# unoshield-v1.net
KiCad netlist of a schematic drawn in EAGLE
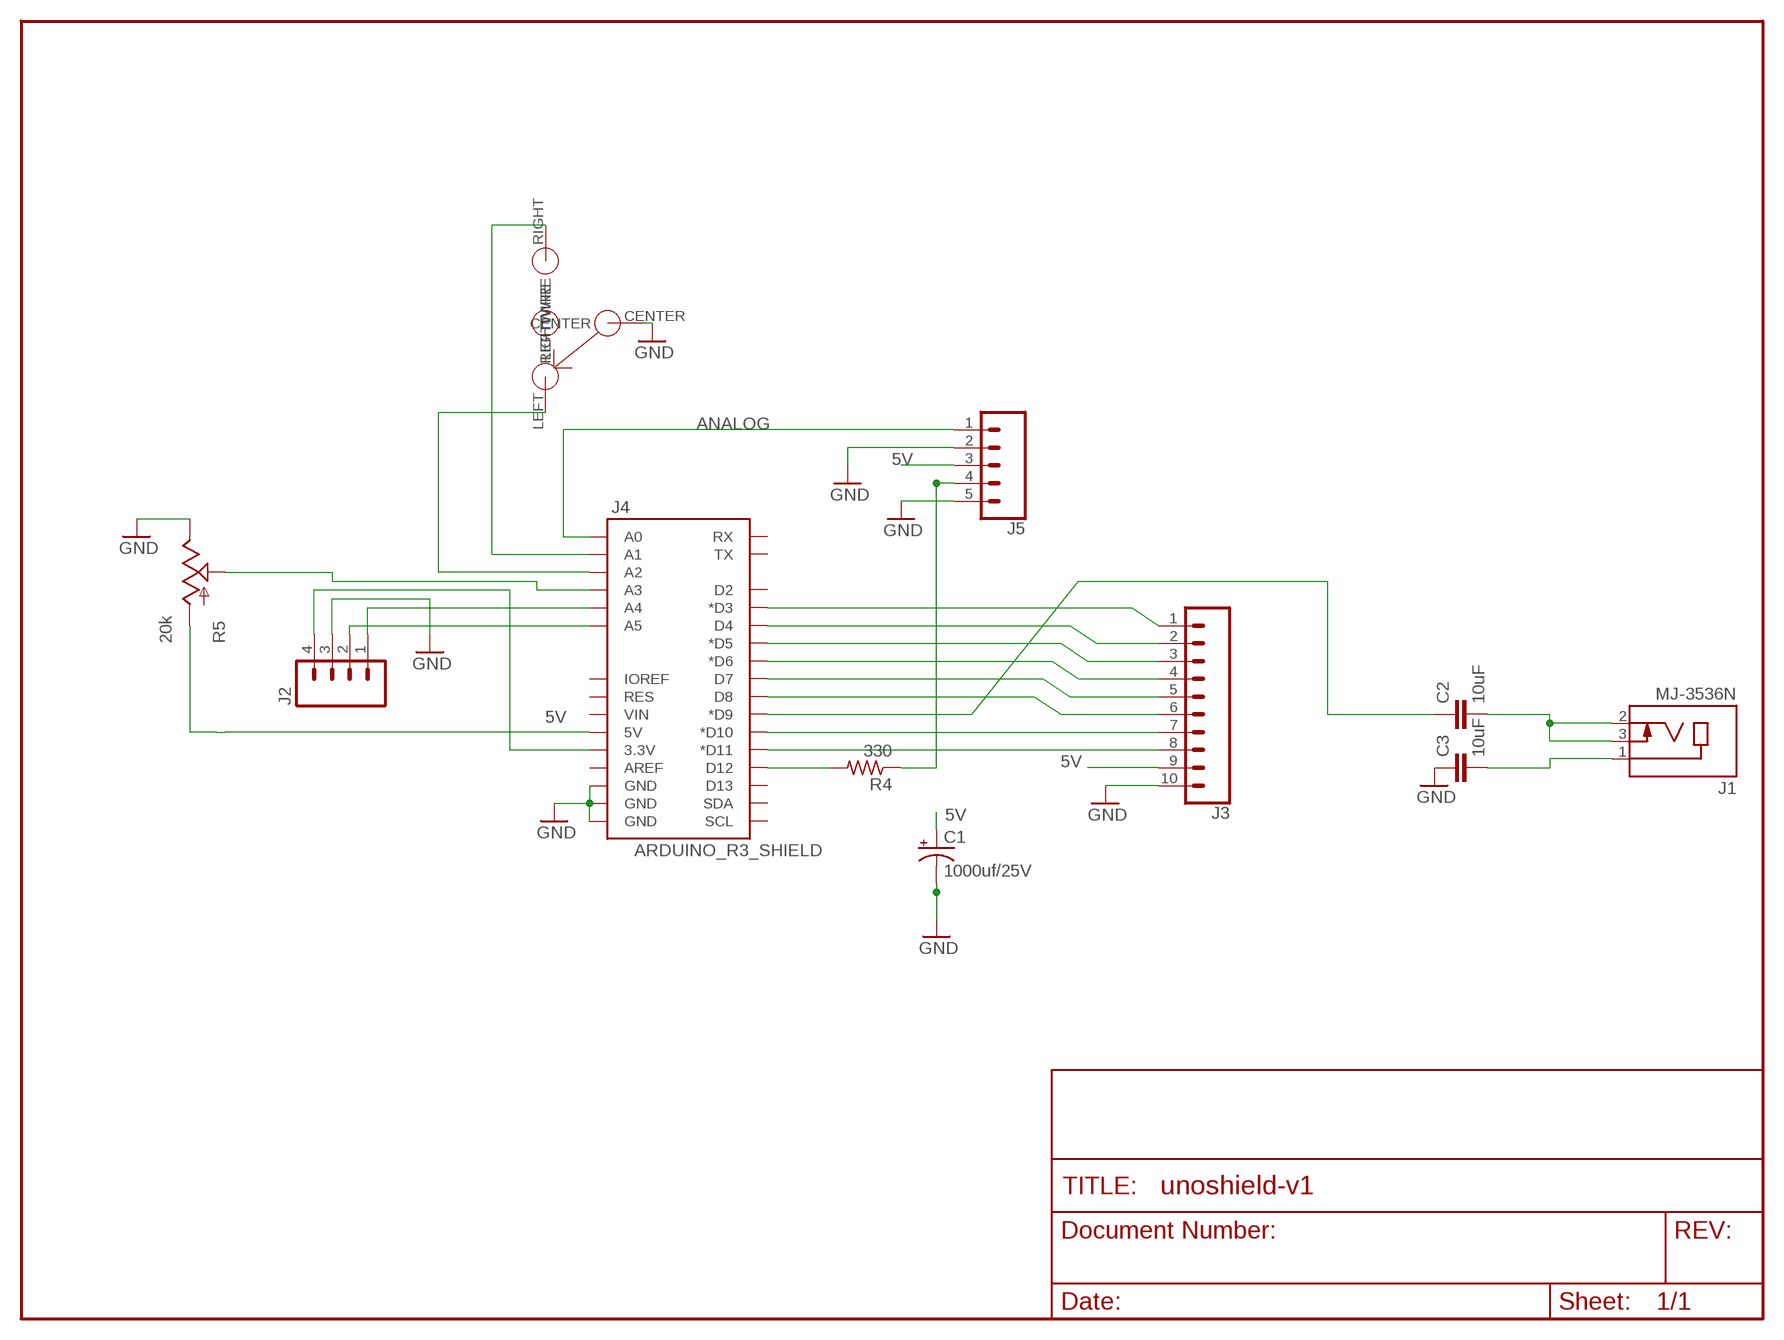
[diagram p0: schematic, sheet 1]

(export (version "E")
  (design (tool "Eeschema 10.0.6"))
  (components
    (comp (ref "C1")
      (value "1000uf/25V")
      (footprint "eagle-import:CPOL-RADIAL-1000UF-25V-KIT")
      (libsource (lib "eagle-import") (part "1000UF-25V(PTH)KIT"))
    )
    (comp (ref "C2")
      (value "10uF")
      (footprint "eagle-import:0805")
      (libsource (lib "eagle-import") (part "10UF-0805-10V-10%"))
    )
    (comp (ref "C3")
      (value "10uF")
      (footprint "eagle-import:0805")
      (libsource (lib "eagle-import") (part "10UF-0805-10V-10%"))
    )
    (comp (ref "J1")
      (value "MJ-3536N")
      (footprint "eagle-import:CUI_MJ-3536N")
      (fields (field (name "MANUFACTURER") "CUI INC"))
      (libsource (lib "eagle-import") (part "MJ-3536N"))
    )
    (comp (ref "J2")
      (value "M04PTH")
      (footprint "eagle-import:1X04")
      (libsource (lib "eagle-import") (part "M04PTH"))
    )
    (comp (ref "J3")
      (value "CONN_10\"")
      (footprint "eagle-import:1X10")
      (libsource (lib "eagle-import") (part "CONN_10{dblquote}"))
    )
    (comp (ref "J4")
      (value "ARDUINO_R3_SHIELD")
      (footprint "eagle-import:UNO_R3_SHIELD")
      (libsource (lib "eagle-import") (part "ARDUINO_R3_SHIELD"))
    )
    (comp (ref "J5")
      (value "CONN_05")
      (footprint "eagle-import:1X05")
      (libsource (lib "eagle-import") (part "CONN_05"))
    )
    (comp (ref "R4")
      (value "330")
      (footprint "eagle-import:R0603")
      (libsource (lib "eagle-import") (part "R-US_R0603"))
    )
    (comp (ref "R5")
      (value "20k")
      (footprint "eagle-import:ALPS_POT_KIT")
      (libsource (lib "eagle-import") (part "POTALPS-KIT"))
    )
    (comp (ref "SW3")
      (value "ON-OFF-ON-360-1013-ND")
      (footprint "eagle-import:360-1013-ND")
      (libsource (lib "eagle-import") (part "ON-OFF-ON-360-1013-ND"))
    )
  )
  (nets
    (net (code "1") (name "/5V") (class "Default")
      (node (ref "C1") (pin "+") (pinfunction "+_+") (pintype "passive"))
      (node (ref "J3") (pin "9") (pinfunction "9_9") (pintype "passive"))
      (node (ref "J4") (pin "5V") (pinfunction "5V_5V") (pintype "bidirectional"))
      (node (ref "J5") (pin "3") (pinfunction "3_3") (pintype "passive"))
      (node (ref "R5") (pin "P$3") (pinfunction "A_P$3") (pintype "passive"))
    )
    (net (code "2") (name "/ANALOG") (class "Default")
      (node (ref "J4") (pin "A0") (pinfunction "A0_A0") (pintype "bidirectional"))
      (node (ref "J5") (pin "1") (pinfunction "1_1") (pintype "passive"))
    )
    (net (code "3") (name "GND") (class "Default")
      (node (ref "C1") (pin "-") (pinfunction "-_-") (pintype "passive"))
      (node (ref "C3") (pin "1") (pinfunction "1_1") (pintype "passive"))
      (node (ref "J2") (pin "3") (pinfunction "3_3") (pintype "passive"))
      (node (ref "J3") (pin "10") (pinfunction "10_10") (pintype "passive"))
      (node (ref "J4") (pin "GND@0") (pinfunction "GND_GND@0") (pintype "bidirectional"))
      (node (ref "J4") (pin "GND@1") (pinfunction "GND_GND@1") (pintype "bidirectional"))
      (node (ref "J4") (pin "GND@2") (pinfunction "GND_GND@2") (pintype "bidirectional"))
      (node (ref "J5") (pin "2") (pinfunction "2_2") (pintype "passive"))
      (node (ref "J5") (pin "5") (pinfunction "5_5") (pintype "passive"))
      (node (ref "R5") (pin "P$1") (pinfunction "E_P$1") (pintype "passive"))
      (node (ref "SW3") (pin "CENTER") (pinfunction "CENTER_CENTER") (pintype "bidirectional"))
    )
    (net (code "4") (name "Net-(C2-Pad2)") (class "Default")
      (node (ref "C2") (pin "2") (pinfunction "2_2") (pintype "passive"))
      (node (ref "J1") (pin "2") (pinfunction "2_2") (pintype "passive"))
      (node (ref "J1") (pin "3") (pinfunction "3_3") (pintype "passive"))
    )
    (net (code "5") (name "Net-(C3-Pad2)") (class "Default")
      (node (ref "C3") (pin "2") (pinfunction "2_2") (pintype "passive"))
      (node (ref "J1") (pin "1") (pinfunction "1_1") (pintype "passive"))
    )
    (net (code "6") (name "Net-(J2-Pad1)") (class "Default")
      (node (ref "J2") (pin "1") (pinfunction "1_1") (pintype "passive"))
      (node (ref "J4") (pin "A4") (pinfunction "A4_A4") (pintype "bidirectional"))
    )
    (net (code "7") (name "Net-(J2-Pad2)") (class "Default")
      (node (ref "J2") (pin "2") (pinfunction "2_2") (pintype "passive"))
      (node (ref "J4") (pin "A5") (pinfunction "A5_A5") (pintype "bidirectional"))
    )
    (net (code "8") (name "Net-(J2-Pad4)") (class "Default")
      (node (ref "J2") (pin "4") (pinfunction "4_4") (pintype "passive"))
      (node (ref "J4") (pin "3.3V") (pinfunction "3.3V_3.3V") (pintype "bidirectional"))
    )
    (net (code "9") (name "Net-(J3-Pad2)") (class "Default")
      (node (ref "J3") (pin "2") (pinfunction "2_2") (pintype "passive"))
      (node (ref "J4") (pin "D4") (pinfunction "D4_D4") (pintype "bidirectional"))
    )
    (net (code "10") (name "Net-(J3-Pad5)") (class "Default")
      (node (ref "J3") (pin "5") (pinfunction "5_5") (pintype "passive"))
      (node (ref "J4") (pin "D7") (pinfunction "D7_D7") (pintype "bidirectional"))
    )
    (net (code "11") (name "Net-(J3-Pad6)") (class "Default")
      (node (ref "J3") (pin "6") (pinfunction "6_6") (pintype "passive"))
      (node (ref "J4") (pin "D8") (pinfunction "D8_D8") (pintype "bidirectional"))
    )
    (net (code "12") (name "Net-(J4-*D3)") (class "Default")
      (node (ref "J3") (pin "1") (pinfunction "1_1") (pintype "passive"))
      (node (ref "J4") (pin "D3") (pinfunction "*D3_D3") (pintype "bidirectional"))
    )
    (net (code "13") (name "Net-(J4-*D5)") (class "Default")
      (node (ref "J3") (pin "3") (pinfunction "3_3") (pintype "passive"))
      (node (ref "J4") (pin "D5") (pinfunction "*D5_D5") (pintype "bidirectional"))
    )
    (net (code "14") (name "Net-(J4-*D6)") (class "Default")
      (node (ref "J3") (pin "4") (pinfunction "4_4") (pintype "passive"))
      (node (ref "J4") (pin "D6") (pinfunction "*D6_D6") (pintype "bidirectional"))
    )
    (net (code "15") (name "Net-(J4-*D9)") (class "Default")
      (node (ref "C2") (pin "1") (pinfunction "1_1") (pintype "passive"))
      (node (ref "J4") (pin "D9") (pinfunction "*D9_D9") (pintype "bidirectional"))
    )
    (net (code "16") (name "Net-(J4-*D10)") (class "Default")
      (node (ref "J3") (pin "7") (pinfunction "7_7") (pintype "passive"))
      (node (ref "J4") (pin "D10") (pinfunction "*D10_D10") (pintype "bidirectional"))
    )
    (net (code "17") (name "Net-(J4-*D11)") (class "Default")
      (node (ref "J3") (pin "8") (pinfunction "8_8") (pintype "passive"))
      (node (ref "J4") (pin "D11") (pinfunction "*D11_D11") (pintype "bidirectional"))
    )
    (net (code "18") (name "Net-(J4-PadD12)") (class "Default")
      (node (ref "J4") (pin "D12") (pinfunction "D12_D12") (pintype "bidirectional"))
      (node (ref "R4") (pin "2") (pinfunction "2_2") (pintype "passive"))
    )
    (net (code "19") (name "Net-(J5-Pad4)") (class "Default")
      (node (ref "J5") (pin "4") (pinfunction "4_4") (pintype "passive"))
      (node (ref "R4") (pin "1") (pinfunction "1_1") (pintype "passive"))
    )
    (net (code "20") (name "Net-(R5-S)") (class "Default")
      (node (ref "J4") (pin "A3") (pinfunction "A3_A3") (pintype "bidirectional"))
      (node (ref "R5") (pin "P$2") (pinfunction "S_P$2") (pintype "passive"))
    )
    (net (code "21") (name "Net-(SW3-LEFTWIRE)") (class "Default")
      (node (ref "J4") (pin "A2") (pinfunction "A2_A2") (pintype "bidirectional"))
      (node (ref "SW3") (pin "LEFT") (pinfunction "LEFTWIRE_LEFT") (pintype "bidirectional"))
    )
    (net (code "22") (name "Net-(SW3-RIGHTWIRE)") (class "Default")
      (node (ref "J4") (pin "A1") (pinfunction "A1_A1") (pintype "bidirectional"))
      (node (ref "SW3") (pin "RIGHT") (pinfunction "RIGHTWIRE_RIGHT") (pintype "bidirectional"))
    )
    (net (code "23") (name "unconnected-(J4-PadAREF)") (class "Default")
      (node (ref "J4") (pin "AREF") (pinfunction "AREF_AREF") (pintype "bidirectional"))
    )
    (net (code "24") (name "unconnected-(J4-PadD2)") (class "Default")
      (node (ref "J4") (pin "D2") (pinfunction "D2_D2") (pintype "bidirectional"))
    )
    (net (code "25") (name "unconnected-(J4-PadD13)") (class "Default")
      (node (ref "J4") (pin "D13") (pinfunction "D13_D13") (pintype "bidirectional"))
    )
    (net (code "26") (name "unconnected-(J4-PadIOREF)") (class "Default")
      (node (ref "J4") (pin "IOREF") (pinfunction "IOREF_IOREF") (pintype "bidirectional"))
    )
    (net (code "27") (name "unconnected-(J4-PadRES)") (class "Default")
      (node (ref "J4") (pin "RES") (pinfunction "RES_RES") (pintype "bidirectional"))
    )
    (net (code "28") (name "unconnected-(J4-PadRX)") (class "Default")
      (node (ref "J4") (pin "RX") (pinfunction "RX_RX") (pintype "bidirectional"))
    )
    (net (code "29") (name "unconnected-(J4-PadSCL)") (class "Default")
      (node (ref "J4") (pin "SCL") (pinfunction "SCL_SCL") (pintype "bidirectional"))
    )
    (net (code "30") (name "unconnected-(J4-PadSDA)") (class "Default")
      (node (ref "J4") (pin "SDA") (pinfunction "SDA_SDA") (pintype "bidirectional"))
    )
    (net (code "31") (name "unconnected-(J4-PadTX)") (class "Default")
      (node (ref "J4") (pin "TX") (pinfunction "TX_TX") (pintype "bidirectional"))
    )
    (net (code "32") (name "unconnected-(J4-PadVIN)") (class "Default")
      (node (ref "J4") (pin "VIN") (pinfunction "VIN_VIN") (pintype "bidirectional"))
    )
  )
)
